# Tilty_Omni.net
KiCad netlist of a schematic drawn in EAGLE
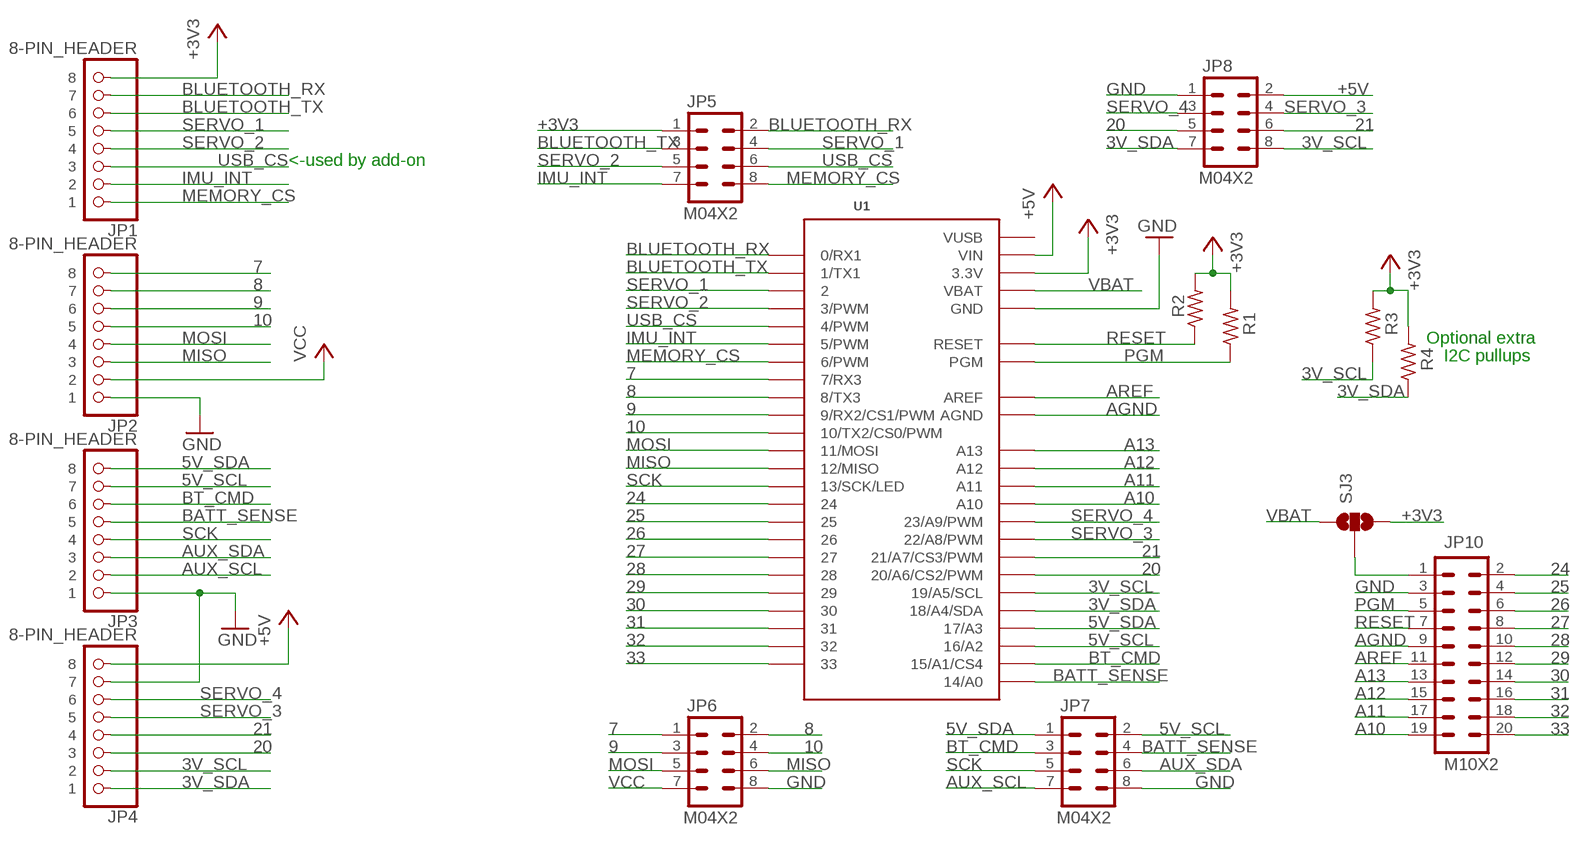
[diagram p0: schematic, sheet 1]

(export (version "E")
  (design (tool "Eeschema 10.0.6"))
  (components
    (comp (ref "JP1")
      (value "8-PIN_HEADER")
      (footprint "eagle-import:8-PIN_RECEPTACLE_LOCK_NO-SS")
      (libsource (lib "eagle-import") (part "8-PIN_HEADER"))
    )
    (comp (ref "JP2")
      (value "8-PIN_HEADER")
      (footprint "eagle-import:8-PIN_RECEPTACLE_LOCK_NO-SS")
      (libsource (lib "eagle-import") (part "8-PIN_HEADER"))
    )
    (comp (ref "JP3")
      (value "8-PIN_HEADER")
      (footprint "eagle-import:8-PIN_RECEPTACLE_LOCK_NO-SS")
      (libsource (lib "eagle-import") (part "8-PIN_HEADER"))
    )
    (comp (ref "JP4")
      (value "8-PIN_HEADER")
      (footprint "eagle-import:8-PIN_RECEPTACLE_LOCK_NO-SS")
      (libsource (lib "eagle-import") (part "8-PIN_HEADER"))
    )
    (comp (ref "JP5")
      (value "M04X2")
      (footprint "eagle-import:2X4")
      (libsource (lib "eagle-import") (part "M04X2"))
    )
    (comp (ref "JP6")
      (value "M04X2")
      (footprint "eagle-import:2X4")
      (libsource (lib "eagle-import") (part "M04X2"))
    )
    (comp (ref "JP7")
      (value "M04X2")
      (footprint "eagle-import:2X4")
      (libsource (lib "eagle-import") (part "M04X2"))
    )
    (comp (ref "JP8")
      (value "M04X2")
      (footprint "eagle-import:2X4")
      (libsource (lib "eagle-import") (part "M04X2"))
    )
    (comp (ref "JP10")
      (value "M10X2")
      (footprint "eagle-import:2X10")
      (libsource (lib "eagle-import") (part "M10X2"))
    )
    (comp (ref "R1")
      (value "10k")
      (footprint "eagle-import:R0603")
      (libsource (lib "eagle-import") (part "R-US_R0603"))
    )
    (comp (ref "R2")
      (value "10k")
      (footprint "eagle-import:R0603")
      (libsource (lib "eagle-import") (part "R-US_R0603"))
    )
    (comp (ref "R3")
      (value "10k")
      (footprint "eagle-import:R0603")
      (libsource (lib "eagle-import") (part "R-US_R0603"))
    )
    (comp (ref "R4")
      (value "10k")
      (footprint "eagle-import:R0603")
      (libsource (lib "eagle-import") (part "R-US_R0603"))
    )
    (comp (ref "SJ3")
      (value "SOLDERJUMPER_2WAYPASTE2&3")
      (footprint "eagle-import:SJ_3_PASTE2&3")
      (libsource (lib "eagle-import") (part "SOLDERJUMPER_2WAYPASTE2&3"))
    )
    (comp (ref "U1")
      (value "TEENSY_3.0_ALLPINS")
      (footprint "eagle-import:TEENSY_3.0_ALLPINS")
      (libsource (lib "eagle-import") (part "TEENSY_3.0_ALLPINS"))
    )
  )
  (nets
    (net (code "1") (name "+3V3") (class "Default")
      (node (ref "JP1") (pin "P$8") (pinfunction "8_P$8") (pintype "passive"))
      (node (ref "JP5") (pin "1") (pinfunction "1_1") (pintype "passive"))
      (node (ref "R1") (pin "2") (pinfunction "2_2") (pintype "passive"))
      (node (ref "R2") (pin "2") (pinfunction "2_2") (pintype "passive"))
      (node (ref "R3") (pin "2") (pinfunction "2_2") (pintype "passive"))
      (node (ref "R4") (pin "2") (pinfunction "2_2") (pintype "passive"))
      (node (ref "SJ3") (pin "3") (pinfunction "3_3") (pintype "passive"))
      (node (ref "U1") (pin "3.3V") (pinfunction "3.3V_3.3V") (pintype "power_in"))
      (node (ref "U1") (pin "3.3V1") (pinfunction "3.3V_3.3V1") (pintype "power_in"))
      (node (ref "U1") (pin "3.3V2") (pinfunction "3.3V_3.3V2") (pintype "power_in"))
    )
    (net (code "2") (name "+5V") (class "Default")
      (node (ref "JP4") (pin "P$8") (pinfunction "8_P$8") (pintype "passive"))
      (node (ref "JP8") (pin "2") (pinfunction "2_2") (pintype "passive"))
      (node (ref "U1") (pin "VIN") (pinfunction "VIN_VIN") (pintype "power_in"))
    )
    (net (code "3") (name "/3V_SCL") (class "Default")
      (node (ref "JP4") (pin "P$2") (pinfunction "2_P$2") (pintype "passive"))
      (node (ref "JP8") (pin "8") (pinfunction "8_8") (pintype "passive"))
      (node (ref "R3") (pin "1") (pinfunction "1_1") (pintype "passive"))
      (node (ref "U1") (pin "19/A5") (pinfunction "19/A5/SCL_19/A5") (pintype "bidirectional"))
    )
    (net (code "4") (name "/3V_SDA") (class "Default")
      (node (ref "JP4") (pin "P$1") (pinfunction "1_P$1") (pintype "passive"))
      (node (ref "JP8") (pin "7") (pinfunction "7_7") (pintype "passive"))
      (node (ref "R4") (pin "1") (pinfunction "1_1") (pintype "passive"))
      (node (ref "U1") (pin "18/A4") (pinfunction "18/A4/SDA_18/A4") (pintype "bidirectional"))
    )
    (net (code "5") (name "/5V_SCL") (class "Default")
      (node (ref "JP3") (pin "P$7") (pinfunction "7_P$7") (pintype "passive"))
      (node (ref "JP7") (pin "2") (pinfunction "2_2") (pintype "passive"))
      (node (ref "U1") (pin "16/A2") (pinfunction "16/A2_16/A2") (pintype "bidirectional"))
    )
    (net (code "6") (name "/5V_SDA") (class "Default")
      (node (ref "JP3") (pin "P$8") (pinfunction "8_P$8") (pintype "passive"))
      (node (ref "JP7") (pin "1") (pinfunction "1_1") (pintype "passive"))
      (node (ref "U1") (pin "17/A3") (pinfunction "17/A3_17/A3") (pintype "bidirectional"))
    )
    (net (code "7") (name "/7") (class "Default")
      (node (ref "JP2") (pin "P$8") (pinfunction "8_P$8") (pintype "passive"))
      (node (ref "JP6") (pin "1") (pinfunction "1_1") (pintype "passive"))
      (node (ref "U1") (pin "7") (pinfunction "7/RX3_7") (pintype "bidirectional"))
    )
    (net (code "8") (name "/8") (class "Default")
      (node (ref "JP2") (pin "P$7") (pinfunction "7_P$7") (pintype "passive"))
      (node (ref "JP6") (pin "2") (pinfunction "2_2") (pintype "passive"))
      (node (ref "U1") (pin "8") (pinfunction "8/TX3_8") (pintype "bidirectional"))
    )
    (net (code "9") (name "/9") (class "Default")
      (node (ref "JP2") (pin "P$6") (pinfunction "6_P$6") (pintype "passive"))
      (node (ref "JP6") (pin "3") (pinfunction "3_3") (pintype "passive"))
      (node (ref "U1") (pin "9") (pinfunction "9/RX2/CS1/PWM_9") (pintype "bidirectional"))
    )
    (net (code "10") (name "/10") (class "Default")
      (node (ref "JP2") (pin "P$5") (pinfunction "5_P$5") (pintype "passive"))
      (node (ref "JP6") (pin "4") (pinfunction "4_4") (pintype "passive"))
      (node (ref "U1") (pin "10") (pinfunction "10/TX2/CS0/PWM_10") (pintype "bidirectional"))
    )
    (net (code "11") (name "/20") (class "Default")
      (node (ref "JP4") (pin "P$3") (pinfunction "3_P$3") (pintype "passive"))
      (node (ref "JP8") (pin "5") (pinfunction "5_5") (pintype "passive"))
      (node (ref "U1") (pin "20/A6") (pinfunction "20/A6/CS2/PWM_20/A6") (pintype "bidirectional"))
    )
    (net (code "12") (name "/21") (class "Default")
      (node (ref "JP4") (pin "P$4") (pinfunction "4_P$4") (pintype "passive"))
      (node (ref "JP8") (pin "6") (pinfunction "6_6") (pintype "passive"))
      (node (ref "U1") (pin "21/A7") (pinfunction "21/A7/CS3/PWM_21/A7") (pintype "bidirectional"))
    )
    (net (code "13") (name "/24") (class "Default")
      (node (ref "JP10") (pin "2") (pinfunction "2_2") (pintype "passive"))
      (node (ref "U1") (pin "24") (pinfunction "24_24") (pintype "bidirectional"))
    )
    (net (code "14") (name "/25") (class "Default")
      (node (ref "JP10") (pin "4") (pinfunction "4_4") (pintype "passive"))
      (node (ref "U1") (pin "25") (pinfunction "25_25") (pintype "bidirectional"))
    )
    (net (code "15") (name "/26") (class "Default")
      (node (ref "JP10") (pin "6") (pinfunction "6_6") (pintype "passive"))
      (node (ref "U1") (pin "26") (pinfunction "26_26") (pintype "bidirectional"))
    )
    (net (code "16") (name "/27") (class "Default")
      (node (ref "JP10") (pin "8") (pinfunction "8_8") (pintype "passive"))
      (node (ref "U1") (pin "27") (pinfunction "27_27") (pintype "bidirectional"))
    )
    (net (code "17") (name "/28") (class "Default")
      (node (ref "JP10") (pin "10") (pinfunction "10_10") (pintype "passive"))
      (node (ref "U1") (pin "28") (pinfunction "28_28") (pintype "bidirectional"))
    )
    (net (code "18") (name "/29") (class "Default")
      (node (ref "JP10") (pin "12") (pinfunction "12_12") (pintype "passive"))
      (node (ref "U1") (pin "29") (pinfunction "29_29") (pintype "bidirectional"))
    )
    (net (code "19") (name "/30") (class "Default")
      (node (ref "JP10") (pin "14") (pinfunction "14_14") (pintype "passive"))
      (node (ref "U1") (pin "30") (pinfunction "30_30") (pintype "bidirectional"))
    )
    (net (code "20") (name "/31") (class "Default")
      (node (ref "JP10") (pin "16") (pinfunction "16_16") (pintype "passive"))
      (node (ref "U1") (pin "31") (pinfunction "31_31") (pintype "bidirectional"))
    )
    (net (code "21") (name "/32") (class "Default")
      (node (ref "JP10") (pin "18") (pinfunction "18_18") (pintype "passive"))
      (node (ref "U1") (pin "32") (pinfunction "32_32") (pintype "bidirectional"))
    )
    (net (code "22") (name "/33") (class "Default")
      (node (ref "JP10") (pin "20") (pinfunction "20_20") (pintype "passive"))
      (node (ref "U1") (pin "33") (pinfunction "33_33") (pintype "bidirectional"))
    )
    (net (code "23") (name "/A10") (class "Default")
      (node (ref "JP10") (pin "19") (pinfunction "19_19") (pintype "passive"))
      (node (ref "U1") (pin "A10") (pinfunction "A10_A10") (pintype "bidirectional"))
    )
    (net (code "24") (name "/A11") (class "Default")
      (node (ref "JP10") (pin "17") (pinfunction "17_17") (pintype "passive"))
      (node (ref "U1") (pin "A11") (pinfunction "A11_A11") (pintype "bidirectional"))
    )
    (net (code "25") (name "/A12") (class "Default")
      (node (ref "JP10") (pin "15") (pinfunction "15_15") (pintype "passive"))
      (node (ref "U1") (pin "A12") (pinfunction "A12_A12") (pintype "bidirectional"))
    )
    (net (code "26") (name "/A13") (class "Default")
      (node (ref "JP10") (pin "13") (pinfunction "13_13") (pintype "passive"))
      (node (ref "U1") (pin "A13") (pinfunction "A13_A13") (pintype "bidirectional"))
    )
    (net (code "27") (name "/AGND") (class "Default")
      (node (ref "JP10") (pin "9") (pinfunction "9_9") (pintype "passive"))
      (node (ref "U1") (pin "AGND") (pinfunction "AGND_AGND") (pintype "power_in"))
    )
    (net (code "28") (name "/AREF") (class "Default")
      (node (ref "JP10") (pin "11") (pinfunction "11_11") (pintype "passive"))
      (node (ref "U1") (pin "AREF") (pinfunction "AREF_AREF") (pintype "power_in"))
    )
    (net (code "29") (name "/AUX_SCL") (class "Default")
      (node (ref "JP3") (pin "P$2") (pinfunction "2_P$2") (pintype "passive"))
      (node (ref "JP7") (pin "7") (pinfunction "7_7") (pintype "passive"))
    )
    (net (code "30") (name "/AUX_SDA") (class "Default")
      (node (ref "JP3") (pin "P$3") (pinfunction "3_P$3") (pintype "passive"))
      (node (ref "JP7") (pin "6") (pinfunction "6_6") (pintype "passive"))
    )
    (net (code "31") (name "/BATT_SENSE") (class "Default")
      (node (ref "JP3") (pin "P$5") (pinfunction "5_P$5") (pintype "passive"))
      (node (ref "JP7") (pin "4") (pinfunction "4_4") (pintype "passive"))
      (node (ref "U1") (pin "14/A0") (pinfunction "14/A0_14/A0") (pintype "bidirectional"))
    )
    (net (code "32") (name "/BLUETOOTH_RX") (class "Default")
      (node (ref "JP1") (pin "P$7") (pinfunction "7_P$7") (pintype "passive"))
      (node (ref "JP5") (pin "2") (pinfunction "2_2") (pintype "passive"))
      (node (ref "U1") (pin "0") (pinfunction "0/RX1_0") (pintype "bidirectional"))
    )
    (net (code "33") (name "/BLUETOOTH_TX") (class "Default")
      (node (ref "JP1") (pin "P$6") (pinfunction "6_P$6") (pintype "passive"))
      (node (ref "JP5") (pin "3") (pinfunction "3_3") (pintype "passive"))
      (node (ref "U1") (pin "1") (pinfunction "1/TX1_1") (pintype "bidirectional"))
    )
    (net (code "34") (name "/BT_CMD") (class "Default")
      (node (ref "JP3") (pin "P$6") (pinfunction "6_P$6") (pintype "passive"))
      (node (ref "JP7") (pin "3") (pinfunction "3_3") (pintype "passive"))
      (node (ref "U1") (pin "15/A1") (pinfunction "15/A1/CS4_15/A1") (pintype "bidirectional"))
    )
    (net (code "35") (name "/IMU_INT") (class "Default")
      (node (ref "JP1") (pin "P$2") (pinfunction "2_P$2") (pintype "passive"))
      (node (ref "JP5") (pin "7") (pinfunction "7_7") (pintype "passive"))
      (node (ref "U1") (pin "5") (pinfunction "5/PWM_5") (pintype "bidirectional"))
    )
    (net (code "36") (name "/MEMORY_CS") (class "Default")
      (node (ref "JP1") (pin "P$1") (pinfunction "1_P$1") (pintype "passive"))
      (node (ref "JP5") (pin "8") (pinfunction "8_8") (pintype "passive"))
      (node (ref "U1") (pin "6") (pinfunction "6/PWM_6") (pintype "bidirectional"))
    )
    (net (code "37") (name "/MISO") (class "Default")
      (node (ref "JP2") (pin "P$3") (pinfunction "3_P$3") (pintype "passive"))
      (node (ref "JP6") (pin "6") (pinfunction "6_6") (pintype "passive"))
      (node (ref "U1") (pin "12") (pinfunction "12/MISO_12") (pintype "bidirectional"))
    )
    (net (code "38") (name "/MOSI") (class "Default")
      (node (ref "JP2") (pin "P$4") (pinfunction "4_P$4") (pintype "passive"))
      (node (ref "JP6") (pin "5") (pinfunction "5_5") (pintype "passive"))
      (node (ref "U1") (pin "11") (pinfunction "11/MOSI_11") (pintype "bidirectional"))
    )
    (net (code "39") (name "/PGM") (class "Default")
      (node (ref "JP10") (pin "5") (pinfunction "5_5") (pintype "passive"))
      (node (ref "R1") (pin "1") (pinfunction "1_1") (pintype "passive"))
      (node (ref "U1") (pin "PGM") (pinfunction "PGM_PGM") (pintype "bidirectional"))
    )
    (net (code "40") (name "/RESET") (class "Default")
      (node (ref "JP10") (pin "7") (pinfunction "7_7") (pintype "passive"))
      (node (ref "R2") (pin "1") (pinfunction "1_1") (pintype "passive"))
      (node (ref "U1") (pin "RESET") (pinfunction "RESET_RESET") (pintype "bidirectional"))
    )
    (net (code "41") (name "/SCK") (class "Default")
      (node (ref "JP3") (pin "P$4") (pinfunction "4_P$4") (pintype "passive"))
      (node (ref "JP7") (pin "5") (pinfunction "5_5") (pintype "passive"))
      (node (ref "U1") (pin "13") (pinfunction "13/SCK/LED_13") (pintype "bidirectional"))
    )
    (net (code "42") (name "/SERVO_1") (class "Default")
      (node (ref "JP1") (pin "P$5") (pinfunction "5_P$5") (pintype "passive"))
      (node (ref "JP5") (pin "4") (pinfunction "4_4") (pintype "passive"))
      (node (ref "U1") (pin "2") (pinfunction "2_2") (pintype "bidirectional"))
    )
    (net (code "43") (name "/SERVO_2") (class "Default")
      (node (ref "JP1") (pin "P$4") (pinfunction "4_P$4") (pintype "passive"))
      (node (ref "JP5") (pin "5") (pinfunction "5_5") (pintype "passive"))
      (node (ref "U1") (pin "3") (pinfunction "3/PWM_3") (pintype "bidirectional"))
    )
    (net (code "44") (name "/SERVO_3") (class "Default")
      (node (ref "JP4") (pin "P$5") (pinfunction "5_P$5") (pintype "passive"))
      (node (ref "JP8") (pin "4") (pinfunction "4_4") (pintype "passive"))
      (node (ref "U1") (pin "22/A8") (pinfunction "22/A8/PWM_22/A8") (pintype "bidirectional"))
    )
    (net (code "45") (name "/SERVO_4") (class "Default")
      (node (ref "JP4") (pin "P$6") (pinfunction "6_P$6") (pintype "passive"))
      (node (ref "JP8") (pin "3") (pinfunction "3_3") (pintype "passive"))
      (node (ref "U1") (pin "23/A9") (pinfunction "23/A9/PWM_23/A9") (pintype "bidirectional"))
    )
    (net (code "46") (name "/USB_CS") (class "Default")
      (node (ref "JP1") (pin "P$3") (pinfunction "3_P$3") (pintype "passive"))
      (node (ref "JP5") (pin "6") (pinfunction "6_6") (pintype "passive"))
      (node (ref "U1") (pin "4") (pinfunction "4/PWM_4") (pintype "bidirectional"))
    )
    (net (code "47") (name "/VBAT") (class "Default")
      (node (ref "SJ3") (pin "1") (pinfunction "1_1") (pintype "passive"))
      (node (ref "U1") (pin "VBAT") (pinfunction "VBAT_VBAT") (pintype "power_in"))
    )
    (net (code "48") (name "/VUSB") (class "Default")
      (node (ref "U1") (pin "VUSB") (pinfunction "VUSB_VUSB") (pintype "power_in"))
    )
    (net (code "49") (name "GND") (class "Default")
      (node (ref "JP10") (pin "3") (pinfunction "3_3") (pintype "passive"))
      (node (ref "JP2") (pin "P$1") (pinfunction "1_P$1") (pintype "passive"))
      (node (ref "JP3") (pin "P$1") (pinfunction "1_P$1") (pintype "passive"))
      (node (ref "JP4") (pin "P$7") (pinfunction "7_P$7") (pintype "passive"))
      (node (ref "JP6") (pin "8") (pinfunction "8_8") (pintype "passive"))
      (node (ref "JP7") (pin "8") (pinfunction "8_8") (pintype "passive"))
      (node (ref "JP8") (pin "1") (pinfunction "1_1") (pintype "passive"))
      (node (ref "U1") (pin "GND") (pinfunction "GND_GND") (pintype "power_in"))
      (node (ref "U1") (pin "GND1") (pinfunction "GND_GND1") (pintype "power_in"))
      (node (ref "U1") (pin "GND2") (pinfunction "GND_GND2") (pintype "power_in"))
    )
    (net (code "50") (name "Net-(JP10-Pad1)") (class "Default")
      (node (ref "JP10") (pin "1") (pinfunction "1_1") (pintype "passive"))
      (node (ref "SJ3") (pin "2") (pinfunction "2_2") (pintype "passive"))
    )
    (net (code "51") (name "VCC") (class "Default")
      (node (ref "JP2") (pin "P$2") (pinfunction "2_P$2") (pintype "passive"))
      (node (ref "JP6") (pin "7") (pinfunction "7_7") (pintype "passive"))
    )
  )
)
